# board.net
KiCad netlist of a schematic drawn in EAGLE
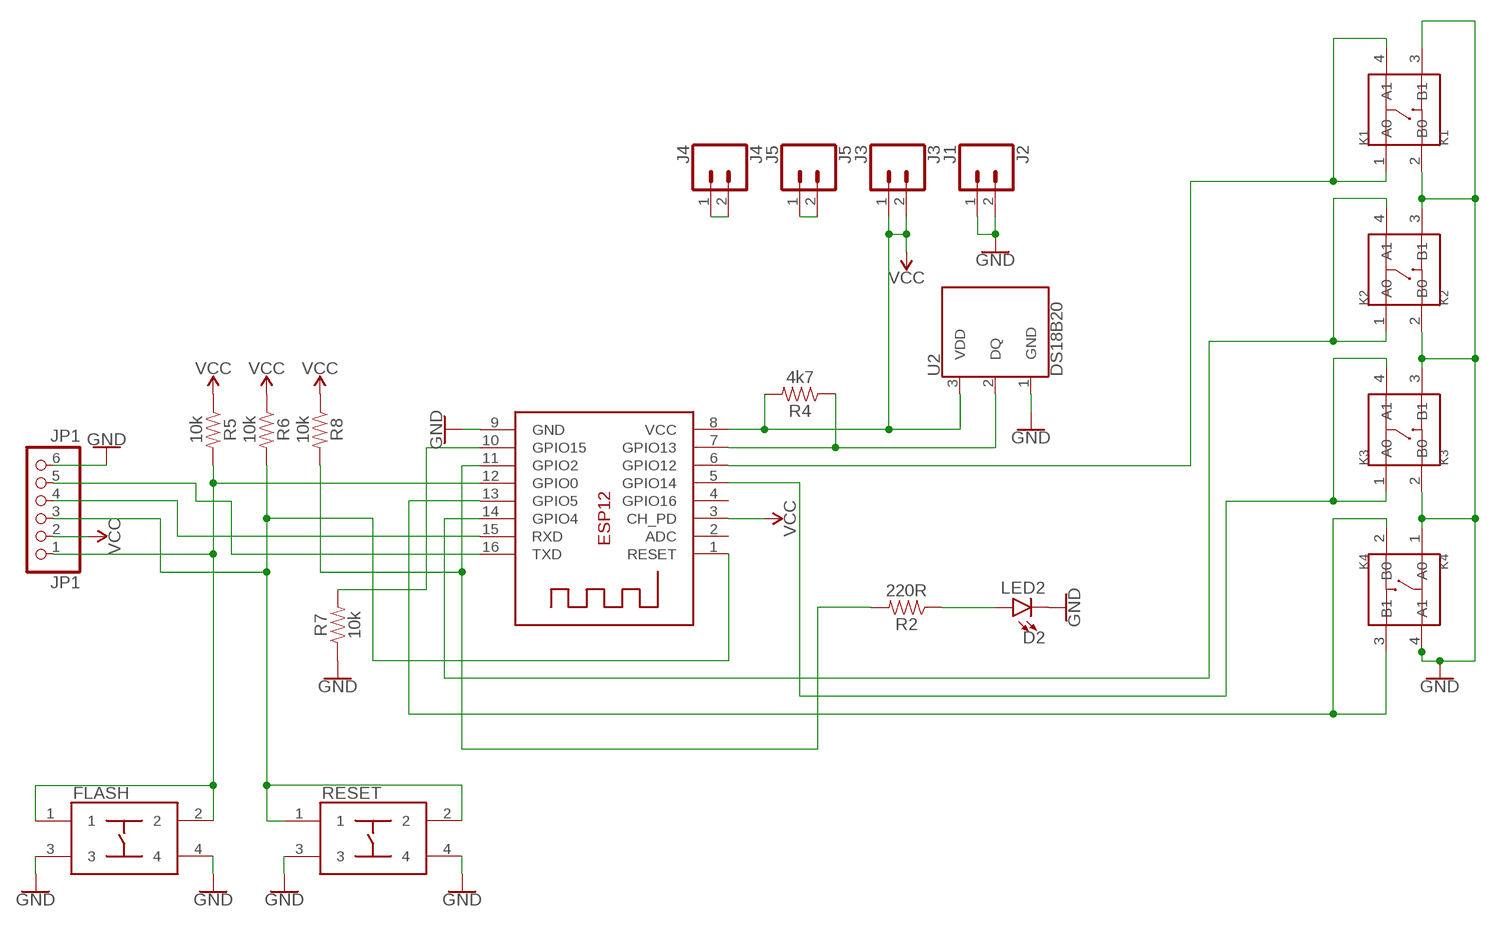
[diagram p0: schematic, sheet 1]

(export (version "E")
  (design (tool "Eeschema 10.0.6"))
  (components
    (comp (ref "D2")
      (value "LED2")
      (footprint "eagle-import:LED_3MM")
      (libsource (lib "eagle-import") (part "LED3MM"))
    )
    (comp (ref "ESP")
      (value "ESP")
      (footprint "eagle-import:ESP-12")
      (libsource (lib "eagle-import") (part "ESP-12"))
    )
    (comp (ref "FLASH")
      (value "TACTILE_SWITCH_DEV")
      (footprint "eagle-import:TACTEIL_SWITCH_PAC")
      (libsource (lib "eagle-import") (part "TACTILE_SWITCH_DEV"))
    )
    (comp (ref "J2")
      (value "J1")
      (footprint "eagle-import:1X02")
      (libsource (lib "eagle-import") (part "CONN_02"))
    )
    (comp (ref "J3")
      (value "J3")
      (footprint "eagle-import:1X02")
      (libsource (lib "eagle-import") (part "CONN_02"))
    )
    (comp (ref "J4")
      (value "J4")
      (footprint "eagle-import:1X02")
      (libsource (lib "eagle-import") (part "CONN_02"))
    )
    (comp (ref "J5")
      (value "J5")
      (footprint "eagle-import:1X02")
      (libsource (lib "eagle-import") (part "CONN_02"))
    )
    (comp (ref "JP1")
      (value "JP1")
      (footprint "eagle-import:1X06")
      (libsource (lib "eagle-import") (part "PINHD-1X6"))
    )
    (comp (ref "K1")
      (value "K1")
      (footprint "eagle-import:SW4-SMD-6.0X6.0X5.0MM")
      (fields (field (name "MPN") "DTSM-62K-S-V-T/R(SN431)"))
      (libsource (lib "eagle-import") (part "SMD-SWITCH-TACTILE-SPST-NO(4P-D6.0MM)"))
    )
    (comp (ref "K2")
      (value "K2")
      (footprint "eagle-import:SW4-SMD-6.0X6.0X5.0MM")
      (fields (field (name "MPN") "DTSM-62K-S-V-T/R(SN431)"))
      (libsource (lib "eagle-import") (part "SMD-SWITCH-TACTILE-SPST-NO(4P-D6.0MM)"))
    )
    (comp (ref "K3")
      (value "K3")
      (footprint "eagle-import:SW4-SMD-6.0X6.0X5.0MM")
      (fields (field (name "MPN") "DTSM-62K-S-V-T/R(SN431)"))
      (libsource (lib "eagle-import") (part "SMD-SWITCH-TACTILE-SPST-NO(4P-D6.0MM)"))
    )
    (comp (ref "K4")
      (value "K4")
      (footprint "eagle-import:SW4-SMD-6.0X6.0X5.0MM")
      (fields (field (name "MPN") "DTSM-62K-S-V-T/R(SN431)"))
      (libsource (lib "eagle-import") (part "SMD-SWITCH-TACTILE-SPST-NO(4P-D6.0MM)"))
    )
    (comp (ref "R2")
      (value "220R")
      (footprint "eagle-import:0603")
      (libsource (lib "eagle-import") (part "1KOHM-0603-1/10W-1%"))
    )
    (comp (ref "R4")
      (value "4k7")
      (footprint "eagle-import:0603")
      (libsource (lib "eagle-import") (part "1KOHM-0603-1/10W-1%"))
    )
    (comp (ref "R5")
      (value "10k")
      (footprint "eagle-import:0603")
      (libsource (lib "eagle-import") (part "1KOHM-0603-1/10W-1%"))
    )
    (comp (ref "R6")
      (value "10k")
      (footprint "eagle-import:0603")
      (libsource (lib "eagle-import") (part "1KOHM-0603-1/10W-1%"))
    )
    (comp (ref "R7")
      (value "10k")
      (footprint "eagle-import:0603")
      (libsource (lib "eagle-import") (part "1KOHM-0603-1/10W-1%"))
    )
    (comp (ref "R8")
      (value "10k")
      (footprint "eagle-import:0603")
      (libsource (lib "eagle-import") (part "1KOHM-0603-1/10W-1%"))
    )
    (comp (ref "RESET")
      (value "TACTILE_SWITCH_DEV")
      (footprint "eagle-import:TACTEIL_SWITCH_PAC")
      (libsource (lib "eagle-import") (part "TACTILE_SWITCH_DEV"))
    )
    (comp (ref "U2")
      (value "DS18B20")
      (footprint "eagle-import:TO-92-AMMO")
      (libsource (lib "eagle-import") (part "DS18B20"))
    )
  )
  (nets
    (net (code "1") (name "GND") (class "Default")
      (node (ref "D2") (pin "K") (pinfunction "C_K") (pintype "passive"))
      (node (ref "ESP") (pin "9") (pinfunction "GND_9") (pintype "power_in"))
      (node (ref "FLASH") (pin "3") (pinfunction "3_3") (pintype "bidirectional"))
      (node (ref "FLASH") (pin "4") (pinfunction "4_4") (pintype "bidirectional"))
      (node (ref "J2") (pin "1") (pinfunction "1_1") (pintype "passive"))
      (node (ref "J2") (pin "2") (pinfunction "2_2") (pintype "passive"))
      (node (ref "JP1") (pin "6") (pinfunction "6_6") (pintype "passive"))
      (node (ref "K1") (pin "2") (pinfunction "B0_2") (pintype "bidirectional"))
      (node (ref "K1") (pin "3") (pinfunction "B1_3") (pintype "bidirectional"))
      (node (ref "K2") (pin "2") (pinfunction "B0_2") (pintype "bidirectional"))
      (node (ref "K2") (pin "3") (pinfunction "B1_3") (pintype "bidirectional"))
      (node (ref "K3") (pin "2") (pinfunction "B0_2") (pintype "bidirectional"))
      (node (ref "K3") (pin "3") (pinfunction "B1_3") (pintype "bidirectional"))
      (node (ref "K4") (pin "1") (pinfunction "A0_1") (pintype "bidirectional"))
      (node (ref "K4") (pin "4") (pinfunction "A1_4") (pintype "bidirectional"))
      (node (ref "R7") (pin "1") (pinfunction "1_1") (pintype "passive"))
      (node (ref "RESET") (pin "3") (pinfunction "3_3") (pintype "bidirectional"))
      (node (ref "RESET") (pin "4") (pinfunction "4_4") (pintype "bidirectional"))
      (node (ref "U2") (pin "1") (pinfunction "GND_1") (pintype "power_in"))
    )
    (net (code "2") (name "Net-(D2-PadA)") (class "Default")
      (node (ref "D2") (pin "A") (pinfunction "A_A") (pintype "passive"))
      (node (ref "R2") (pin "1") (pinfunction "1_1") (pintype "passive"))
    )
    (net (code "3") (name "Net-(ESP-GPIO0)") (class "Default")
      (node (ref "ESP") (pin "12") (pinfunction "GPIO0_12") (pintype "bidirectional"))
      (node (ref "FLASH") (pin "1") (pinfunction "1_1") (pintype "bidirectional"))
      (node (ref "FLASH") (pin "2") (pinfunction "2_2") (pintype "bidirectional"))
      (node (ref "JP1") (pin "1") (pinfunction "1_1") (pintype "passive"))
      (node (ref "R5") (pin "2") (pinfunction "2_2") (pintype "passive"))
    )
    (net (code "4") (name "Net-(ESP-GPIO2)") (class "Default")
      (node (ref "ESP") (pin "11") (pinfunction "GPIO2_11") (pintype "bidirectional"))
      (node (ref "R2") (pin "2") (pinfunction "2_2") (pintype "passive"))
      (node (ref "R8") (pin "2") (pinfunction "2_2") (pintype "passive"))
    )
    (net (code "5") (name "Net-(ESP-GPIO4)") (class "Default")
      (node (ref "ESP") (pin "14") (pinfunction "GPIO4_14") (pintype "bidirectional"))
      (node (ref "K2") (pin "1") (pinfunction "A0_1") (pintype "bidirectional"))
      (node (ref "K2") (pin "4") (pinfunction "A1_4") (pintype "bidirectional"))
    )
    (net (code "6") (name "Net-(ESP-GPIO5)") (class "Default")
      (node (ref "ESP") (pin "13") (pinfunction "GPIO5_13") (pintype "bidirectional"))
      (node (ref "K4") (pin "2") (pinfunction "B0_2") (pintype "bidirectional"))
      (node (ref "K4") (pin "3") (pinfunction "B1_3") (pintype "bidirectional"))
    )
    (net (code "7") (name "Net-(ESP-GPIO12)") (class "Default")
      (node (ref "ESP") (pin "6") (pinfunction "GPIO12_6") (pintype "bidirectional"))
      (node (ref "K1") (pin "1") (pinfunction "A0_1") (pintype "bidirectional"))
      (node (ref "K1") (pin "4") (pinfunction "A1_4") (pintype "bidirectional"))
    )
    (net (code "8") (name "Net-(ESP-GPIO13)") (class "Default")
      (node (ref "ESP") (pin "7") (pinfunction "GPIO13_7") (pintype "bidirectional"))
      (node (ref "R4") (pin "1") (pinfunction "1_1") (pintype "passive"))
      (node (ref "U2") (pin "2") (pinfunction "DQ_2") (pintype "bidirectional"))
    )
    (net (code "9") (name "Net-(ESP-GPIO14)") (class "Default")
      (node (ref "ESP") (pin "5") (pinfunction "GPIO14_5") (pintype "bidirectional"))
      (node (ref "K3") (pin "1") (pinfunction "A0_1") (pintype "bidirectional"))
      (node (ref "K3") (pin "4") (pinfunction "A1_4") (pintype "bidirectional"))
    )
    (net (code "10") (name "Net-(ESP-GPIO15)") (class "Default")
      (node (ref "ESP") (pin "10") (pinfunction "GPIO15_10") (pintype "bidirectional"))
      (node (ref "R7") (pin "2") (pinfunction "2_2") (pintype "passive"))
    )
    (net (code "11") (name "Net-(ESP-RESET)") (class "Default")
      (node (ref "ESP") (pin "1") (pinfunction "RESET_1") (pintype "input"))
      (node (ref "JP1") (pin "3") (pinfunction "3_3") (pintype "passive"))
      (node (ref "R6") (pin "2") (pinfunction "2_2") (pintype "passive"))
      (node (ref "RESET") (pin "1") (pinfunction "1_1") (pintype "bidirectional"))
      (node (ref "RESET") (pin "2") (pinfunction "2_2") (pintype "bidirectional"))
    )
    (net (code "12") (name "Net-(ESP-RXD)") (class "Default")
      (node (ref "ESP") (pin "15") (pinfunction "RXD_15") (pintype "input"))
      (node (ref "JP1") (pin "4") (pinfunction "4_4") (pintype "passive"))
    )
    (net (code "13") (name "Net-(ESP-TXD)") (class "Default")
      (node (ref "ESP") (pin "16") (pinfunction "TXD_16") (pintype "output"))
      (node (ref "JP1") (pin "5") (pinfunction "5_5") (pintype "passive"))
    )
    (net (code "14") (name "Net-(J4-Pad1)") (class "Default")
      (node (ref "J4") (pin "1") (pinfunction "1_1") (pintype "passive"))
      (node (ref "J4") (pin "2") (pinfunction "2_2") (pintype "passive"))
    )
    (net (code "15") (name "Net-(J5-Pad1)") (class "Default")
      (node (ref "J5") (pin "1") (pinfunction "1_1") (pintype "passive"))
      (node (ref "J5") (pin "2") (pinfunction "2_2") (pintype "passive"))
    )
    (net (code "16") (name "VCC") (class "Default")
      (node (ref "ESP") (pin "3") (pinfunction "CH_PD_3") (pintype "input"))
      (node (ref "ESP") (pin "8") (pinfunction "VCC_8") (pintype "power_in"))
      (node (ref "J3") (pin "1") (pinfunction "1_1") (pintype "passive"))
      (node (ref "J3") (pin "2") (pinfunction "2_2") (pintype "passive"))
      (node (ref "JP1") (pin "2") (pinfunction "2_2") (pintype "passive"))
      (node (ref "R4") (pin "2") (pinfunction "2_2") (pintype "passive"))
      (node (ref "R5") (pin "1") (pinfunction "1_1") (pintype "passive"))
      (node (ref "R6") (pin "1") (pinfunction "1_1") (pintype "passive"))
      (node (ref "R8") (pin "1") (pinfunction "1_1") (pintype "passive"))
      (node (ref "U2") (pin "3") (pinfunction "VDD_3") (pintype "power_in"))
    )
    (net (code "17") (name "unconnected-(ESP-ADC-Pad2)") (class "Default")
      (node (ref "ESP") (pin "2") (pinfunction "ADC_2") (pintype "passive"))
    )
    (net (code "18") (name "unconnected-(ESP-GPIO16-Pad4)") (class "Default")
      (node (ref "ESP") (pin "4") (pinfunction "GPIO16_4") (pintype "bidirectional"))
    )
  )
)
